# Placa_20_1_1.net
KiCad netlist of a schematic drawn in EAGLE
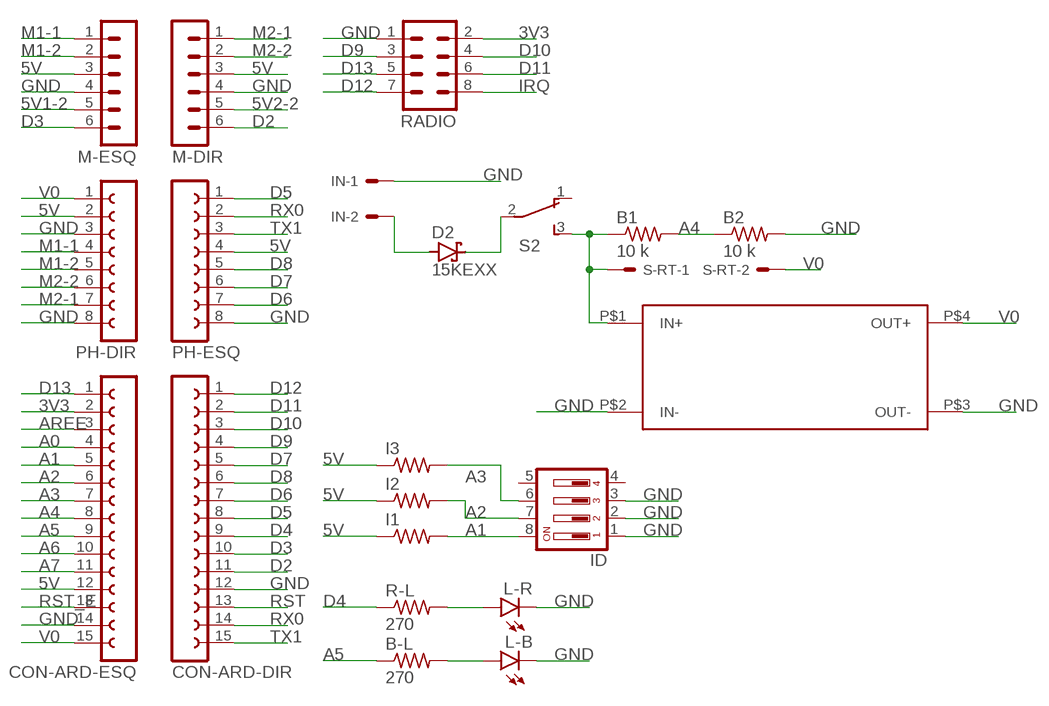
[diagram p0: schematic, sheet 1]

(export (version "E")
  (design (tool "Eeschema 10.0.6"))
  (components
    (comp (ref "B-L")
      (value "270")
      (footprint "eagle-import:0207_10")
      (libsource (lib "eagle-import") (part "R-US_0207/10"))
    )
    (comp (ref "B1")
      (value "10 k")
      (footprint "eagle-import:0207_10")
      (libsource (lib "eagle-import") (part "R-US_0207/10"))
    )
    (comp (ref "B2")
      (value "10 k")
      (footprint "eagle-import:0207_10")
      (libsource (lib "eagle-import") (part "R-US_0207/10"))
    )
    (comp (ref "CON-ARD-DIR")
      (value "FE15-1")
      (footprint "eagle-import:FE15")
      (libsource (lib "eagle-import") (part "FE15-1"))
    )
    (comp (ref "CON-ARD-ESQ")
      (value "FE15-1")
      (footprint "eagle-import:FE15")
      (fields (field (name "SPICEPREFIX") "X"))
      (libsource (lib "eagle-import") (part "FE15-1"))
    )
    (comp (ref "D2")
      (value "15KEXX")
      (footprint "eagle-import:CB429-17")
      (libsource (lib "eagle-import") (part "15KEXX"))
    )
    (comp (ref "I1")
      (value "R-US_0207/10")
      (footprint "eagle-import:0207_10")
      (libsource (lib "eagle-import") (part "R-US_0207/10"))
    )
    (comp (ref "I2")
      (value "R-US_0207/10")
      (footprint "eagle-import:0207_10")
      (libsource (lib "eagle-import") (part "R-US_0207/10"))
    )
    (comp (ref "I3")
      (value "R-US_0207/10")
      (footprint "eagle-import:0207_10")
      (libsource (lib "eagle-import") (part "R-US_0207/10"))
    )
    (comp (ref "ID")
      (value "DA04")
      (footprint "eagle-import:DA-04")
      (fields (field (name "MPN") "MCDA04"))
      (libsource (lib "eagle-import") (part "DA04"))
    )
    (comp (ref "IN")
      (value "332-02")
      (footprint "eagle-import:332-02")
      (libsource (lib "eagle-import") (part "332-02"))
    )
    (comp (ref "L-B")
      (value "LED5MM")
      (footprint "eagle-import:LED5MM")
      (libsource (lib "eagle-import") (part "LED5MM"))
    )
    (comp (ref "L-R")
      (value "LED5MM")
      (footprint "eagle-import:LED5MM")
      (libsource (lib "eagle-import") (part "LED5MM"))
    )
    (comp (ref "M-DIR")
      (value "MA06-1")
      (footprint "eagle-import:MA06-1")
      (libsource (lib "eagle-import") (part "MA06-1"))
    )
    (comp (ref "M-ESQ")
      (value "MA06-1")
      (footprint "eagle-import:MA06-1")
      (libsource (lib "eagle-import") (part "MA06-1"))
    )
    (comp (ref "PH-DIR")
      (value "FE08-1")
      (footprint "eagle-import:FE08")
      (libsource (lib "eagle-import") (part "FE08-1"))
    )
    (comp (ref "PH-ESQ")
      (value "FE08-1")
      (footprint "eagle-import:FE08")
      (libsource (lib "eagle-import") (part "FE08-1"))
    )
    (comp (ref "R-L")
      (value "270")
      (footprint "eagle-import:0207_10")
      (libsource (lib "eagle-import") (part "R-US_0207/10"))
    )
    (comp (ref "RADIO")
      (value "MA04-2")
      (footprint "eagle-import:MA04-2")
      (libsource (lib "eagle-import") (part "MA04-2"))
    )
    (comp (ref "REGULADOR-DE-TENSÃO")
      (value "REGULADOR")
      (footprint "eagle-import:REGULADOR-FP")
      (libsource (lib "eagle-import") (part "REGULADOR"))
    )
    (comp (ref "S-RT")
      (value "332-02")
      (footprint "eagle-import:332-02")
      (libsource (lib "eagle-import") (part "332-02"))
    )
    (comp (ref "S2")
      (value "TL36YO")
      (footprint "eagle-import:TL3XYO")
      (libsource (lib "eagle-import") (part "TL36YO"))
    )
  )
  (nets
    (net (code "1") (name "3V3") (class "Default")
      (node (ref "CON-ARD-ESQ") (pin "2") (pinfunction "2_2") (pintype "passive"))
      (node (ref "RADIO") (pin "2") (pinfunction "2_2") (pintype "passive"))
    )
    (net (code "2") (name "5V") (class "Default")
      (node (ref "CON-ARD-ESQ") (pin "12") (pinfunction "12_12") (pintype "passive"))
      (node (ref "I1") (pin "1") (pinfunction "1_1") (pintype "passive"))
      (node (ref "I2") (pin "1") (pinfunction "1_1") (pintype "passive"))
      (node (ref "I3") (pin "1") (pinfunction "1_1") (pintype "passive"))
      (node (ref "M-DIR") (pin "3") (pinfunction "3_3") (pintype "passive"))
      (node (ref "M-ESQ") (pin "3") (pinfunction "3_3") (pintype "passive"))
      (node (ref "PH-DIR") (pin "2") (pinfunction "2_2") (pintype "passive"))
      (node (ref "PH-ESQ") (pin "4") (pinfunction "4_4") (pintype "passive"))
    )
    (net (code "3") (name "5V1-2") (class "Default")
      (node (ref "M-ESQ") (pin "5") (pinfunction "5_5") (pintype "passive"))
    )
    (net (code "4") (name "5V2-2") (class "Default")
      (node (ref "M-DIR") (pin "5") (pinfunction "5_5") (pintype "passive"))
    )
    (net (code "5") (name "A0") (class "Default")
      (node (ref "CON-ARD-ESQ") (pin "4") (pinfunction "4_4") (pintype "passive"))
    )
    (net (code "6") (name "A1") (class "Default")
      (node (ref "CON-ARD-ESQ") (pin "5") (pinfunction "5_5") (pintype "passive"))
      (node (ref "I1") (pin "2") (pinfunction "2_2") (pintype "passive"))
      (node (ref "ID") (pin "8") (pinfunction "8_8") (pintype "passive"))
    )
    (net (code "7") (name "A2") (class "Default")
      (node (ref "CON-ARD-ESQ") (pin "6") (pinfunction "6_6") (pintype "passive"))
      (node (ref "I2") (pin "2") (pinfunction "2_2") (pintype "passive"))
      (node (ref "ID") (pin "7") (pinfunction "7_7") (pintype "passive"))
    )
    (net (code "8") (name "A3") (class "Default")
      (node (ref "CON-ARD-ESQ") (pin "7") (pinfunction "7_7") (pintype "passive"))
      (node (ref "I3") (pin "2") (pinfunction "2_2") (pintype "passive"))
      (node (ref "ID") (pin "6") (pinfunction "6_6") (pintype "passive"))
    )
    (net (code "9") (name "A4") (class "Default")
      (node (ref "B1") (pin "2") (pinfunction "2_2") (pintype "passive"))
      (node (ref "B2") (pin "1") (pinfunction "1_1") (pintype "passive"))
      (node (ref "CON-ARD-ESQ") (pin "8") (pinfunction "8_8") (pintype "passive"))
    )
    (net (code "10") (name "A5") (class "Default")
      (node (ref "B-L") (pin "1") (pinfunction "1_1") (pintype "passive"))
      (node (ref "CON-ARD-ESQ") (pin "9") (pinfunction "9_9") (pintype "passive"))
    )
    (net (code "11") (name "A6") (class "Default")
      (node (ref "CON-ARD-ESQ") (pin "10") (pinfunction "10_10") (pintype "passive"))
    )
    (net (code "12") (name "A7") (class "Default")
      (node (ref "CON-ARD-ESQ") (pin "11") (pinfunction "11_11") (pintype "passive"))
    )
    (net (code "13") (name "AREE") (class "Default")
      (node (ref "CON-ARD-ESQ") (pin "3") (pinfunction "3_3") (pintype "passive"))
    )
    (net (code "14") (name "D2") (class "Default")
      (node (ref "CON-ARD-DIR") (pin "11") (pinfunction "11_11") (pintype "passive"))
      (node (ref "M-DIR") (pin "6") (pinfunction "6_6") (pintype "passive"))
    )
    (net (code "15") (name "D3") (class "Default")
      (node (ref "CON-ARD-DIR") (pin "10") (pinfunction "10_10") (pintype "passive"))
      (node (ref "M-ESQ") (pin "6") (pinfunction "6_6") (pintype "passive"))
    )
    (net (code "16") (name "D4") (class "Default")
      (node (ref "CON-ARD-DIR") (pin "9") (pinfunction "9_9") (pintype "passive"))
      (node (ref "R-L") (pin "1") (pinfunction "1_1") (pintype "passive"))
    )
    (net (code "17") (name "D5") (class "Default")
      (node (ref "CON-ARD-DIR") (pin "8") (pinfunction "8_8") (pintype "passive"))
      (node (ref "PH-ESQ") (pin "1") (pinfunction "1_1") (pintype "passive"))
    )
    (net (code "18") (name "D6") (class "Default")
      (node (ref "CON-ARD-DIR") (pin "7") (pinfunction "7_7") (pintype "passive"))
      (node (ref "PH-ESQ") (pin "7") (pinfunction "7_7") (pintype "passive"))
    )
    (net (code "19") (name "D7") (class "Default")
      (node (ref "CON-ARD-DIR") (pin "5") (pinfunction "5_5") (pintype "passive"))
      (node (ref "PH-ESQ") (pin "6") (pinfunction "6_6") (pintype "passive"))
    )
    (net (code "20") (name "D8") (class "Default")
      (node (ref "CON-ARD-DIR") (pin "6") (pinfunction "6_6") (pintype "passive"))
      (node (ref "PH-ESQ") (pin "5") (pinfunction "5_5") (pintype "passive"))
    )
    (net (code "21") (name "D9") (class "Default")
      (node (ref "CON-ARD-DIR") (pin "4") (pinfunction "4_4") (pintype "passive"))
      (node (ref "RADIO") (pin "3") (pinfunction "3_3") (pintype "passive"))
    )
    (net (code "22") (name "D10") (class "Default")
      (node (ref "CON-ARD-DIR") (pin "3") (pinfunction "3_3") (pintype "passive"))
      (node (ref "RADIO") (pin "4") (pinfunction "4_4") (pintype "passive"))
    )
    (net (code "23") (name "D11") (class "Default")
      (node (ref "CON-ARD-DIR") (pin "2") (pinfunction "2_2") (pintype "passive"))
      (node (ref "RADIO") (pin "6") (pinfunction "6_6") (pintype "passive"))
    )
    (net (code "24") (name "D12") (class "Default")
      (node (ref "CON-ARD-DIR") (pin "1") (pinfunction "1_1") (pintype "passive"))
      (node (ref "RADIO") (pin "7") (pinfunction "7_7") (pintype "passive"))
    )
    (net (code "25") (name "D13") (class "Default")
      (node (ref "CON-ARD-ESQ") (pin "1") (pinfunction "1_1") (pintype "passive"))
      (node (ref "RADIO") (pin "5") (pinfunction "5_5") (pintype "passive"))
    )
    (net (code "26") (name "GND") (class "Default")
      (node (ref "B2") (pin "2") (pinfunction "2_2") (pintype "passive"))
      (node (ref "CON-ARD-DIR") (pin "12") (pinfunction "12_12") (pintype "passive"))
      (node (ref "CON-ARD-ESQ") (pin "14") (pinfunction "14_14") (pintype "passive"))
      (node (ref "ID") (pin "1") (pinfunction "1_1") (pintype "passive"))
      (node (ref "ID") (pin "2") (pinfunction "2_2") (pintype "passive"))
      (node (ref "ID") (pin "3") (pinfunction "3_3") (pintype "passive"))
      (node (ref "IN") (pin "1") (pinfunction "S_1") (pintype "passive"))
      (node (ref "L-B") (pin "K") (pinfunction "C_K") (pintype "passive"))
      (node (ref "L-R") (pin "K") (pinfunction "C_K") (pintype "passive"))
      (node (ref "M-DIR") (pin "4") (pinfunction "4_4") (pintype "passive"))
      (node (ref "M-ESQ") (pin "4") (pinfunction "4_4") (pintype "passive"))
      (node (ref "PH-DIR") (pin "3") (pinfunction "3_3") (pintype "passive"))
      (node (ref "PH-DIR") (pin "8") (pinfunction "8_8") (pintype "passive"))
      (node (ref "PH-ESQ") (pin "8") (pinfunction "8_8") (pintype "passive"))
      (node (ref "RADIO") (pin "1") (pinfunction "1_1") (pintype "passive"))
      (node (ref "REGULADOR-DE-TENSÃO") (pin "P$2") (pinfunction "IN-_P$2") (pintype "bidirectional"))
      (node (ref "REGULADOR-DE-TENSÃO") (pin "P$3") (pinfunction "OUT-_P$3") (pintype "bidirectional"))
    )
    (net (code "27") (name "IRQ") (class "Default")
      (node (ref "RADIO") (pin "8") (pinfunction "8_8") (pintype "passive"))
    )
    (net (code "28") (name "M1-1") (class "Default")
      (node (ref "M-ESQ") (pin "1") (pinfunction "1_1") (pintype "passive"))
      (node (ref "PH-DIR") (pin "4") (pinfunction "4_4") (pintype "passive"))
    )
    (net (code "29") (name "M1-2") (class "Default")
      (node (ref "M-ESQ") (pin "2") (pinfunction "2_2") (pintype "passive"))
      (node (ref "PH-DIR") (pin "5") (pinfunction "5_5") (pintype "passive"))
    )
    (net (code "30") (name "M2-1") (class "Default")
      (node (ref "M-DIR") (pin "1") (pinfunction "1_1") (pintype "passive"))
      (node (ref "PH-DIR") (pin "7") (pinfunction "7_7") (pintype "passive"))
    )
    (net (code "31") (name "M2-2") (class "Default")
      (node (ref "M-DIR") (pin "2") (pinfunction "2_2") (pintype "passive"))
      (node (ref "PH-DIR") (pin "6") (pinfunction "6_6") (pintype "passive"))
    )
    (net (code "32") (name "Net-(B-L-Pad2)") (class "Default")
      (node (ref "B-L") (pin "2") (pinfunction "2_2") (pintype "passive"))
      (node (ref "L-B") (pin "A") (pinfunction "A_A") (pintype "passive"))
    )
    (net (code "33") (name "Net-(INB-S)") (class "Default")
      (node (ref "D2") (pin "A") (pinfunction "A_A") (pintype "passive"))
      (node (ref "IN") (pin "2") (pinfunction "S_2") (pintype "passive"))
    )
    (net (code "34") (name "Net-(L-R-PadA)") (class "Default")
      (node (ref "L-R") (pin "A") (pinfunction "A_A") (pintype "passive"))
      (node (ref "R-L") (pin "2") (pinfunction "2_2") (pintype "passive"))
    )
    (net (code "35") (name "Net-(REGULADOR-DE-TENSÃO-IN+)") (class "Default")
      (node (ref "B1") (pin "1") (pinfunction "1_1") (pintype "passive"))
      (node (ref "REGULADOR-DE-TENSÃO") (pin "P$1") (pinfunction "IN+_P$1") (pintype "bidirectional"))
      (node (ref "S-RT") (pin "1") (pinfunction "S_1") (pintype "passive"))
      (node (ref "S2") (pin "3") (pinfunction "S_3") (pintype "passive"))
    )
    (net (code "36") (name "Net-(S2-P)") (class "Default")
      (node (ref "D2") (pin "C") (pinfunction "C_C") (pintype "passive"))
      (node (ref "S2") (pin "2") (pinfunction "P_2") (pintype "passive"))
    )
    (net (code "37") (name "RST") (class "Default")
      (node (ref "CON-ARD-DIR") (pin "13") (pinfunction "13_13") (pintype "passive"))
    )
    (net (code "38") (name "RST_E") (class "Default")
      (node (ref "CON-ARD-ESQ") (pin "13") (pinfunction "13_13") (pintype "passive"))
    )
    (net (code "39") (name "RX0") (class "Default")
      (node (ref "CON-ARD-DIR") (pin "14") (pinfunction "14_14") (pintype "passive"))
      (node (ref "PH-ESQ") (pin "2") (pinfunction "2_2") (pintype "passive"))
    )
    (net (code "40") (name "TX1") (class "Default")
      (node (ref "CON-ARD-DIR") (pin "15") (pinfunction "15_15") (pintype "passive"))
      (node (ref "PH-ESQ") (pin "3") (pinfunction "3_3") (pintype "passive"))
    )
    (net (code "41") (name "V0") (class "Default")
      (node (ref "CON-ARD-ESQ") (pin "15") (pinfunction "15_15") (pintype "passive"))
      (node (ref "PH-DIR") (pin "1") (pinfunction "1_1") (pintype "passive"))
      (node (ref "REGULADOR-DE-TENSÃO") (pin "P$4") (pinfunction "OUT+_P$4") (pintype "bidirectional"))
      (node (ref "S-RT") (pin "2") (pinfunction "S_2") (pintype "passive"))
    )
    (net (code "42") (name "unconnected-(ID-Pad4)") (class "Default")
      (node (ref "ID") (pin "4") (pinfunction "4_4") (pintype "passive"))
    )
    (net (code "43") (name "unconnected-(ID-Pad5)") (class "Default")
      (node (ref "ID") (pin "5") (pinfunction "5_5") (pintype "passive"))
    )
    (net (code "44") (name "unconnected-(S2-O-Pad1)") (class "Default")
      (node (ref "S2") (pin "1") (pinfunction "O_1") (pintype "passive"))
    )
  )
)
